# Interface.net
KiCad netlist of a schematic drawn in EAGLE
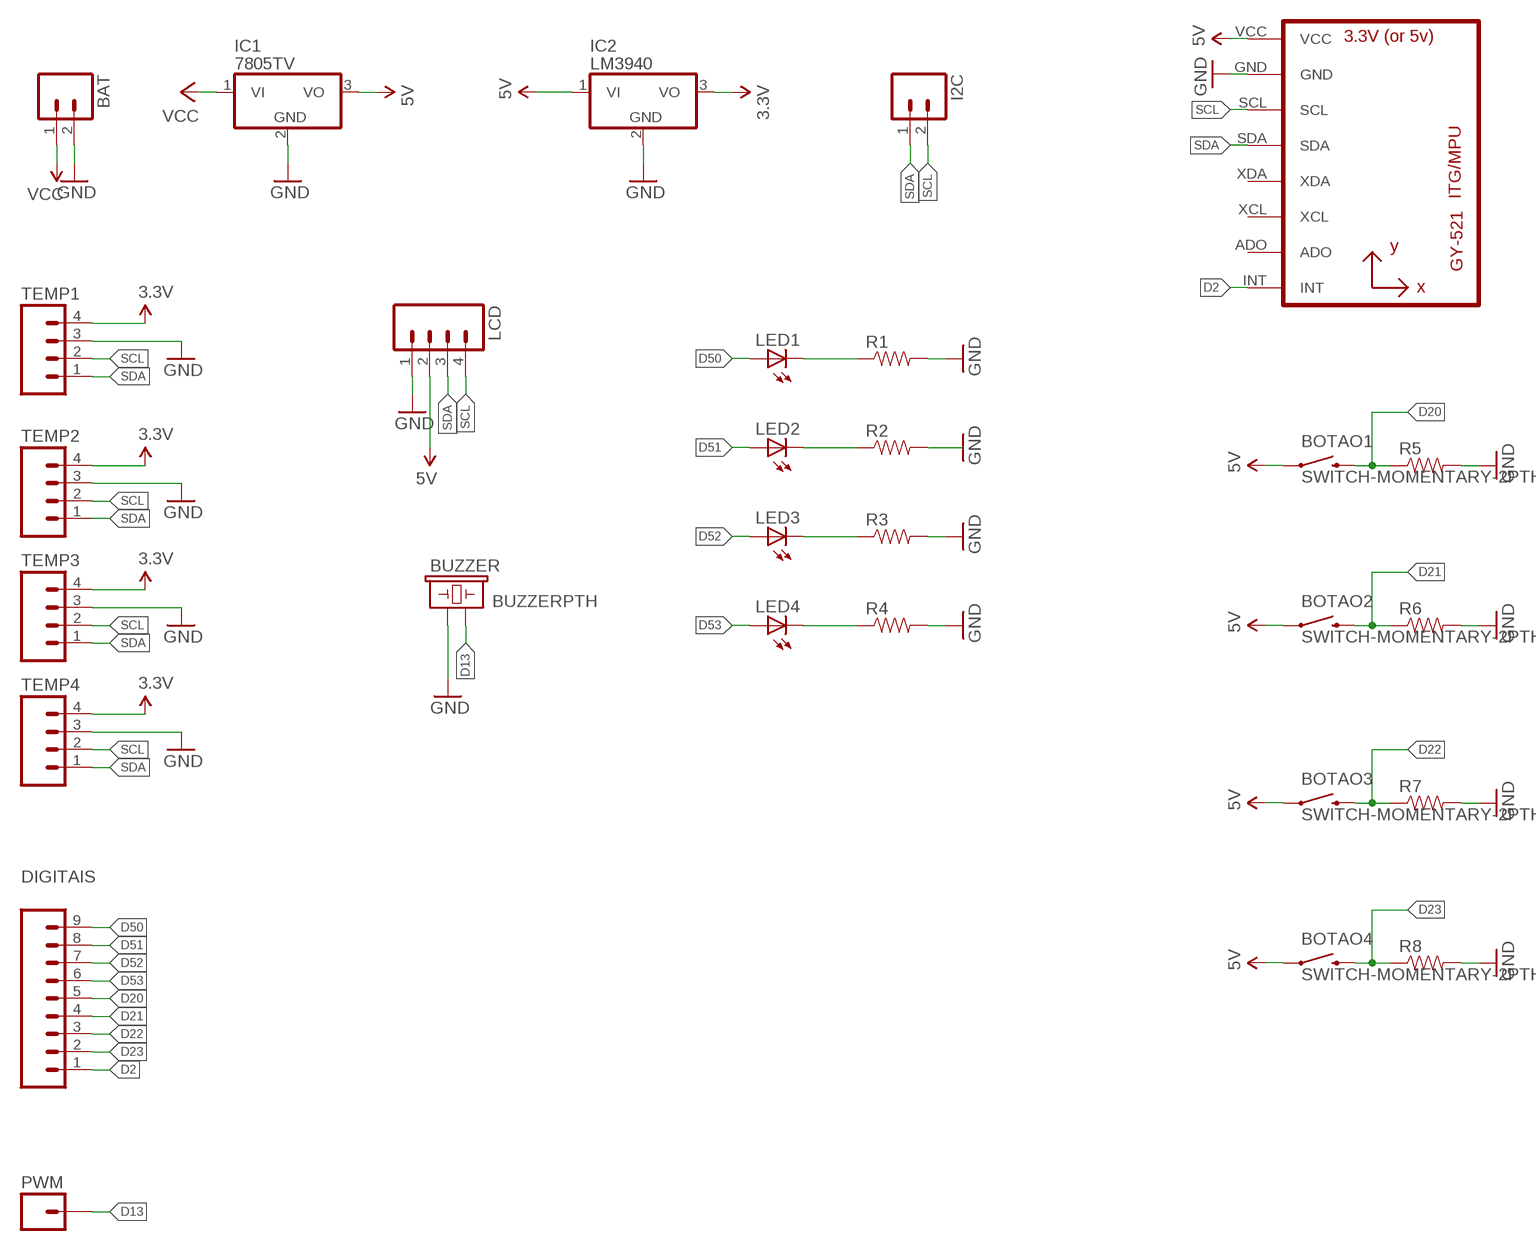
[diagram p0: schematic, sheet 1]

(export (version "E")
  (design (tool "Eeschema 10.0.6"))
  (components
    (comp (ref "BAT")
      (value "M02PTH")
      (footprint "eagle-import:1X02")
      (libsource (lib "eagle-import") (part "M02PTH"))
    )
    (comp (ref "BOTAO1")
      (value "SWITCH-MOMENTARY-2PTH")
      (footprint "eagle-import:TACTILE-PTH")
      (libsource (lib "eagle-import") (part "SWITCH-MOMENTARY-2PTH"))
    )
    (comp (ref "BOTAO2")
      (value "SWITCH-MOMENTARY-2PTH")
      (footprint "eagle-import:TACTILE-PTH")
      (libsource (lib "eagle-import") (part "SWITCH-MOMENTARY-2PTH"))
    )
    (comp (ref "BOTAO3")
      (value "SWITCH-MOMENTARY-2PTH")
      (footprint "eagle-import:TACTILE-PTH")
      (libsource (lib "eagle-import") (part "SWITCH-MOMENTARY-2PTH"))
    )
    (comp (ref "BOTAO4")
      (value "SWITCH-MOMENTARY-2PTH")
      (footprint "eagle-import:TACTILE-PTH")
      (libsource (lib "eagle-import") (part "SWITCH-MOMENTARY-2PTH"))
    )
    (comp (ref "BUZZER")
      (value "BUZZERPTH")
      (footprint "eagle-import:BUZZER-12MM")
      (libsource (lib "eagle-import") (part "BUZZERPTH"))
    )
    (comp (ref "DIGITAIS")
      (value "M09")
      (footprint "eagle-import:1X09")
      (libsource (lib "eagle-import") (part "M09"))
    )
    (comp (ref "I2C")
      (value "M02PTH")
      (footprint "eagle-import:1X02")
      (libsource (lib "eagle-import") (part "M02PTH"))
    )
    (comp (ref "IC1")
      (value "7805TV")
      (footprint "eagle-import:TO220V")
      (libsource (lib "eagle-import") (part "78TV05"))
    )
    (comp (ref "IC2")
      (value "LM3940")
      (footprint "eagle-import:TO220V")
      (libsource (lib "eagle-import") (part "78TV05"))
    )
    (comp (ref "LCD")
      (value "M04PTH")
      (footprint "eagle-import:1X04")
      (libsource (lib "eagle-import") (part "M04PTH"))
    )
    (comp (ref "LED1")
      (value "LED5MM")
      (footprint "eagle-import:LED5MM")
      (libsource (lib "eagle-import") (part "LED5MM"))
    )
    (comp (ref "LED2")
      (value "LED5MM")
      (footprint "eagle-import:LED5MM")
      (libsource (lib "eagle-import") (part "LED5MM"))
    )
    (comp (ref "LED3")
      (value "LED5MM")
      (footprint "eagle-import:LED5MM")
      (libsource (lib "eagle-import") (part "LED5MM"))
    )
    (comp (ref "LED4")
      (value "LED5MM")
      (footprint "eagle-import:LED5MM")
      (libsource (lib "eagle-import") (part "LED5MM"))
    )
    (comp (ref "PWM")
      (value "M01PTH")
      (footprint "eagle-import:1X01")
      (libsource (lib "eagle-import") (part "M01PTH"))
    )
    (comp (ref "R1")
      (value "RESISTOREZ")
      (footprint "eagle-import:AXIAL-0.3EZ")
      (libsource (lib "eagle-import") (part "RESISTOREZ"))
    )
    (comp (ref "R2")
      (value "RESISTOREZ")
      (footprint "eagle-import:AXIAL-0.3EZ")
      (libsource (lib "eagle-import") (part "RESISTOREZ"))
    )
    (comp (ref "R3")
      (value "RESISTOREZ")
      (footprint "eagle-import:AXIAL-0.3EZ")
      (libsource (lib "eagle-import") (part "RESISTOREZ"))
    )
    (comp (ref "R4")
      (value "RESISTOREZ")
      (footprint "eagle-import:AXIAL-0.3EZ")
      (libsource (lib "eagle-import") (part "RESISTOREZ"))
    )
    (comp (ref "R5")
      (value "RESISTOREZ")
      (footprint "eagle-import:AXIAL-0.3EZ")
      (libsource (lib "eagle-import") (part "RESISTOREZ"))
    )
    (comp (ref "R6")
      (value "RESISTOREZ")
      (footprint "eagle-import:AXIAL-0.3EZ")
      (libsource (lib "eagle-import") (part "RESISTOREZ"))
    )
    (comp (ref "R7")
      (value "RESISTOREZ")
      (footprint "eagle-import:AXIAL-0.3EZ")
      (libsource (lib "eagle-import") (part "RESISTOREZ"))
    )
    (comp (ref "R8")
      (value "RESISTOREZ")
      (footprint "eagle-import:AXIAL-0.3EZ")
      (libsource (lib "eagle-import") (part "RESISTOREZ"))
    )
    (comp (ref "TEMP1")
      (value "M04PTH")
      (footprint "eagle-import:1X04")
      (libsource (lib "eagle-import") (part "M04PTH"))
    )
    (comp (ref "TEMP2")
      (value "M04PTH")
      (footprint "eagle-import:1X04")
      (libsource (lib "eagle-import") (part "M04PTH"))
    )
    (comp (ref "TEMP3")
      (value "M04PTH")
      (footprint "eagle-import:1X04")
      (libsource (lib "eagle-import") (part "M04PTH"))
    )
    (comp (ref "TEMP4")
      (value "M04PTH")
      (footprint "eagle-import:1X04")
      (libsource (lib "eagle-import") (part "M04PTH"))
    )
    (comp (ref "U1")
      (value "GY-521MPU6050")
      (footprint "eagle-import:GY-521")
      (libsource (lib "eagle-import") (part "GY-521MPU6050"))
    )
  )
  (nets
    (net (code "1") (name "3.3V") (class "Default")
      (node (ref "IC2") (pin "3") (pinfunction "VO_3") (pintype "passive"))
      (node (ref "TEMP1") (pin "4") (pinfunction "4_4") (pintype "passive"))
      (node (ref "TEMP2") (pin "4") (pinfunction "4_4") (pintype "passive"))
      (node (ref "TEMP3") (pin "4") (pinfunction "4_4") (pintype "passive"))
      (node (ref "TEMP4") (pin "4") (pinfunction "4_4") (pintype "passive"))
    )
    (net (code "2") (name "5V") (class "Default")
      (node (ref "BOTAO1") (pin "1") (pinfunction "1_1") (pintype "passive"))
      (node (ref "BOTAO2") (pin "1") (pinfunction "1_1") (pintype "passive"))
      (node (ref "BOTAO3") (pin "1") (pinfunction "1_1") (pintype "passive"))
      (node (ref "BOTAO4") (pin "1") (pinfunction "1_1") (pintype "passive"))
      (node (ref "IC1") (pin "3") (pinfunction "VO_3") (pintype "passive"))
      (node (ref "IC2") (pin "1") (pinfunction "VI_1") (pintype "input"))
      (node (ref "LCD") (pin "2") (pinfunction "2_2") (pintype "passive"))
      (node (ref "U1") (pin "VCC") (pinfunction "VCC_VCC") (pintype "bidirectional"))
    )
    (net (code "3") (name "D2") (class "Default")
      (node (ref "DIGITAIS") (pin "1") (pinfunction "1_1") (pintype "passive"))
      (node (ref "U1") (pin "INT") (pinfunction "INT_INT") (pintype "bidirectional"))
    )
    (net (code "4") (name "D13") (class "Default")
      (node (ref "BUZZER") (pin "-") (pinfunction "2_-") (pintype "passive"))
      (node (ref "PWM") (pin "1") (pinfunction "1_1") (pintype "passive"))
    )
    (net (code "5") (name "D20") (class "Default")
      (node (ref "BOTAO1") (pin "3") (pinfunction "2_3") (pintype "passive"))
      (node (ref "DIGITAIS") (pin "5") (pinfunction "5_5") (pintype "passive"))
      (node (ref "R5") (pin "P$1") (pinfunction "1_P$1") (pintype "passive"))
    )
    (net (code "6") (name "D21") (class "Default")
      (node (ref "BOTAO2") (pin "3") (pinfunction "2_3") (pintype "passive"))
      (node (ref "DIGITAIS") (pin "4") (pinfunction "4_4") (pintype "passive"))
      (node (ref "R6") (pin "P$1") (pinfunction "1_P$1") (pintype "passive"))
    )
    (net (code "7") (name "D22") (class "Default")
      (node (ref "BOTAO3") (pin "3") (pinfunction "2_3") (pintype "passive"))
      (node (ref "DIGITAIS") (pin "3") (pinfunction "3_3") (pintype "passive"))
      (node (ref "R7") (pin "P$1") (pinfunction "1_P$1") (pintype "passive"))
    )
    (net (code "8") (name "D23") (class "Default")
      (node (ref "BOTAO4") (pin "3") (pinfunction "2_3") (pintype "passive"))
      (node (ref "DIGITAIS") (pin "2") (pinfunction "2_2") (pintype "passive"))
      (node (ref "R8") (pin "P$1") (pinfunction "1_P$1") (pintype "passive"))
    )
    (net (code "9") (name "D50") (class "Default")
      (node (ref "DIGITAIS") (pin "9") (pinfunction "9_9") (pintype "passive"))
      (node (ref "LED1") (pin "A") (pinfunction "A_A") (pintype "passive"))
    )
    (net (code "10") (name "D51") (class "Default")
      (node (ref "DIGITAIS") (pin "8") (pinfunction "8_8") (pintype "passive"))
      (node (ref "LED2") (pin "A") (pinfunction "A_A") (pintype "passive"))
    )
    (net (code "11") (name "D52") (class "Default")
      (node (ref "DIGITAIS") (pin "7") (pinfunction "7_7") (pintype "passive"))
      (node (ref "LED3") (pin "A") (pinfunction "A_A") (pintype "passive"))
    )
    (net (code "12") (name "D53") (class "Default")
      (node (ref "DIGITAIS") (pin "6") (pinfunction "6_6") (pintype "passive"))
      (node (ref "LED4") (pin "A") (pinfunction "A_A") (pintype "passive"))
    )
    (net (code "13") (name "GND") (class "Default")
      (node (ref "BAT") (pin "2") (pinfunction "2_2") (pintype "passive"))
      (node (ref "BUZZER") (pin "+") (pinfunction "1_+") (pintype "passive"))
      (node (ref "IC1") (pin "2") (pinfunction "GND_2") (pintype "passive"))
      (node (ref "IC2") (pin "2") (pinfunction "GND_2") (pintype "passive"))
      (node (ref "LCD") (pin "1") (pinfunction "1_1") (pintype "passive"))
      (node (ref "R1") (pin "P$2") (pinfunction "2_P$2") (pintype "passive"))
      (node (ref "R2") (pin "P$2") (pinfunction "2_P$2") (pintype "passive"))
      (node (ref "R3") (pin "P$2") (pinfunction "2_P$2") (pintype "passive"))
      (node (ref "R4") (pin "P$2") (pinfunction "2_P$2") (pintype "passive"))
      (node (ref "R5") (pin "P$2") (pinfunction "2_P$2") (pintype "passive"))
      (node (ref "R6") (pin "P$2") (pinfunction "2_P$2") (pintype "passive"))
      (node (ref "R7") (pin "P$2") (pinfunction "2_P$2") (pintype "passive"))
      (node (ref "R8") (pin "P$2") (pinfunction "2_P$2") (pintype "passive"))
      (node (ref "TEMP1") (pin "3") (pinfunction "3_3") (pintype "passive"))
      (node (ref "TEMP2") (pin "3") (pinfunction "3_3") (pintype "passive"))
      (node (ref "TEMP3") (pin "3") (pinfunction "3_3") (pintype "passive"))
      (node (ref "TEMP4") (pin "3") (pinfunction "3_3") (pintype "passive"))
      (node (ref "U1") (pin "GND") (pinfunction "GND_GND") (pintype "bidirectional"))
    )
    (net (code "14") (name "Net-(LED1-C)") (class "Default")
      (node (ref "LED1") (pin "K") (pinfunction "C_K") (pintype "passive"))
      (node (ref "R1") (pin "P$1") (pinfunction "1_P$1") (pintype "passive"))
    )
    (net (code "15") (name "Net-(LED2-C)") (class "Default")
      (node (ref "LED2") (pin "K") (pinfunction "C_K") (pintype "passive"))
      (node (ref "R2") (pin "P$1") (pinfunction "1_P$1") (pintype "passive"))
    )
    (net (code "16") (name "Net-(LED3-C)") (class "Default")
      (node (ref "LED3") (pin "K") (pinfunction "C_K") (pintype "passive"))
      (node (ref "R3") (pin "P$1") (pinfunction "1_P$1") (pintype "passive"))
    )
    (net (code "17") (name "Net-(LED4-C)") (class "Default")
      (node (ref "LED4") (pin "K") (pinfunction "C_K") (pintype "passive"))
      (node (ref "R4") (pin "P$1") (pinfunction "1_P$1") (pintype "passive"))
    )
    (net (code "18") (name "SCL") (class "Default")
      (node (ref "I2C") (pin "2") (pinfunction "2_2") (pintype "passive"))
      (node (ref "LCD") (pin "4") (pinfunction "4_4") (pintype "passive"))
      (node (ref "TEMP1") (pin "2") (pinfunction "2_2") (pintype "passive"))
      (node (ref "TEMP2") (pin "2") (pinfunction "2_2") (pintype "passive"))
      (node (ref "TEMP3") (pin "2") (pinfunction "2_2") (pintype "passive"))
      (node (ref "TEMP4") (pin "2") (pinfunction "2_2") (pintype "passive"))
      (node (ref "U1") (pin "SCL") (pinfunction "SCL_SCL") (pintype "bidirectional"))
    )
    (net (code "19") (name "SDA") (class "Default")
      (node (ref "I2C") (pin "1") (pinfunction "1_1") (pintype "passive"))
      (node (ref "LCD") (pin "3") (pinfunction "3_3") (pintype "passive"))
      (node (ref "TEMP1") (pin "1") (pinfunction "1_1") (pintype "passive"))
      (node (ref "TEMP2") (pin "1") (pinfunction "1_1") (pintype "passive"))
      (node (ref "TEMP3") (pin "1") (pinfunction "1_1") (pintype "passive"))
      (node (ref "TEMP4") (pin "1") (pinfunction "1_1") (pintype "passive"))
      (node (ref "U1") (pin "SDA") (pinfunction "SDA_SDA") (pintype "bidirectional"))
    )
    (net (code "20") (name "VCC") (class "Default")
      (node (ref "BAT") (pin "1") (pinfunction "1_1") (pintype "passive"))
      (node (ref "IC1") (pin "1") (pinfunction "VI_1") (pintype "input"))
    )
    (net (code "21") (name "unconnected-(U1-PadADO)") (class "Default")
      (node (ref "U1") (pin "ADO") (pinfunction "ADO_ADO") (pintype "bidirectional"))
    )
    (net (code "22") (name "unconnected-(U1-PadXCL)") (class "Default")
      (node (ref "U1") (pin "XCL") (pinfunction "XCL_XCL") (pintype "bidirectional"))
    )
    (net (code "23") (name "unconnected-(U1-PadXDA)") (class "Default")
      (node (ref "U1") (pin "XDA") (pinfunction "XDA_XDA") (pintype "bidirectional"))
    )
  )
)
